# jtag-switch.net
KiCad netlist of a schematic drawn in Altium Designer
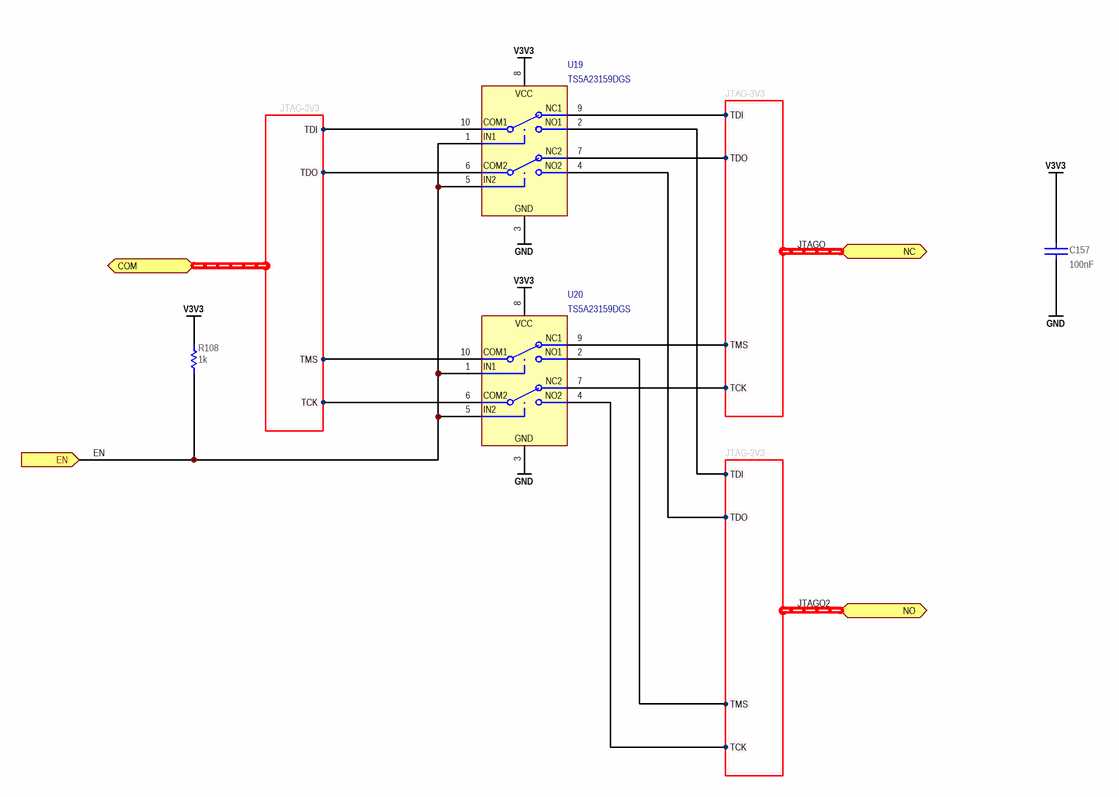
[diagram p0: jtag-switch.SchDoc]

(export (version "E")
  (design (tool "Eeschema 10.0.6"))
  (components
    (comp (ref "C157")
      (value "100nF")
      (footprint "CAPC100X50X55L25N")
      (description "Ceramic Capacitor 100nF ±10% 50V X7R 0402")
      (fields (field (name "MANUFACTURER") "Murata") (field (name "TOLERANCE") "±10%"))
      (libsource (lib "generic") (part "CAP"))
    )
    (comp (ref "R108")
      (value "1k")
      (footprint "RESC1005X40N")
      (description "Thick Film Resistor 1k ±1% 0.1W 50V 0402")
      (fields (field (name "MANUFACTURER") "Panasonic") (field (name "TOLERANCE") "±1%"))
      (libsource (lib "generic") (part "RES"))
    )
    (comp (ref "U19")
      (value "TS5A23159DGS")
      (footprint "DGS-10")
      (description "2-Channel SPDT Analog Switch")
      (fields (field (name "MANUFACTURER") "Texas Instruments"))
      (libsource (lib "ti") (part "TS5A23159DGS"))
    )
    (comp (ref "U20")
      (value "TS5A23159DGS")
      (footprint "DGS-10")
      (description "2-Channel SPDT Analog Switch")
      (fields (field (name "MANUFACTURER") "Texas Instruments"))
      (libsource (lib "ti") (part "TS5A23159DGS"))
    )
  )
  (nets
    (net (code "4") (name "/EN") (class "Default")
      (node (ref "R108") (pin "1") (pinfunction "1_1") (pintype "passive"))
      (node (ref "U19") (pin "1") (pinfunction "IN1_1") (pintype "passive"))
      (node (ref "U19") (pin "5") (pinfunction "IN2_5") (pintype "passive"))
      (node (ref "U20") (pin "1") (pinfunction "IN1_1") (pintype "passive"))
      (node (ref "U20") (pin "5") (pinfunction "IN2_5") (pintype "passive"))
    )
    (net (code "8") (name "GND") (class "Default")
      (node (ref "C157") (pin "1") (pinfunction "1_1") (pintype "passive"))
      (node (ref "U19") (pin "3") (pinfunction "GND_3") (pintype "passive"))
      (node (ref "U20") (pin "3") (pinfunction "GND_3") (pintype "passive"))
    )
    (net (code "9") (name "V3V3") (class "Default")
      (node (ref "C157") (pin "2") (pinfunction "2_2") (pintype "passive"))
      (node (ref "R108") (pin "2") (pinfunction "2_2") (pintype "passive"))
      (node (ref "U19") (pin "8") (pinfunction "VCC_8") (pintype "passive"))
      (node (ref "U20") (pin "8") (pinfunction "VCC_8") (pintype "passive"))
    )
    (net (code "10") (name "unconnected-(U19-COM1-Pad10)") (class "Default")
      (node (ref "U19") (pin "10") (pinfunction "COM1_10") (pintype "passive"))
    )
    (net (code "11") (name "unconnected-(U19-COM2-Pad6)") (class "Default")
      (node (ref "U19") (pin "6") (pinfunction "COM2_6") (pintype "passive"))
    )
    (net (code "12") (name "unconnected-(U19-NC1-Pad9)") (class "Default")
      (node (ref "U19") (pin "9") (pinfunction "NC1_9") (pintype "passive"))
    )
    (net (code "13") (name "unconnected-(U19-NC2-Pad7)") (class "Default")
      (node (ref "U19") (pin "7") (pinfunction "NC2_7") (pintype "passive"))
    )
    (net (code "14") (name "unconnected-(U19-NO1-Pad2)") (class "Default")
      (node (ref "U19") (pin "2") (pinfunction "NO1_2") (pintype "passive"))
    )
    (net (code "15") (name "unconnected-(U19-NO2-Pad4)") (class "Default")
      (node (ref "U19") (pin "4") (pinfunction "NO2_4") (pintype "passive"))
    )
    (net (code "16") (name "unconnected-(U20-COM1-Pad10)") (class "Default")
      (node (ref "U20") (pin "10") (pinfunction "COM1_10") (pintype "passive"))
    )
    (net (code "17") (name "unconnected-(U20-COM2-Pad6)") (class "Default")
      (node (ref "U20") (pin "6") (pinfunction "COM2_6") (pintype "passive"))
    )
    (net (code "18") (name "unconnected-(U20-NC1-Pad9)") (class "Default")
      (node (ref "U20") (pin "9") (pinfunction "NC1_9") (pintype "passive"))
    )
    (net (code "19") (name "unconnected-(U20-NC2-Pad7)") (class "Default")
      (node (ref "U20") (pin "7") (pinfunction "NC2_7") (pintype "passive"))
    )
    (net (code "20") (name "unconnected-(U20-NO1-Pad2)") (class "Default")
      (node (ref "U20") (pin "2") (pinfunction "NO1_2") (pintype "passive"))
    )
    (net (code "21") (name "unconnected-(U20-NO2-Pad4)") (class "Default")
      (node (ref "U20") (pin "4") (pinfunction "NO2_4") (pintype "passive"))
    )
  )
)
